# AdaptorEthernet485.net
KiCad netlist of a schematic drawn in EAGLE
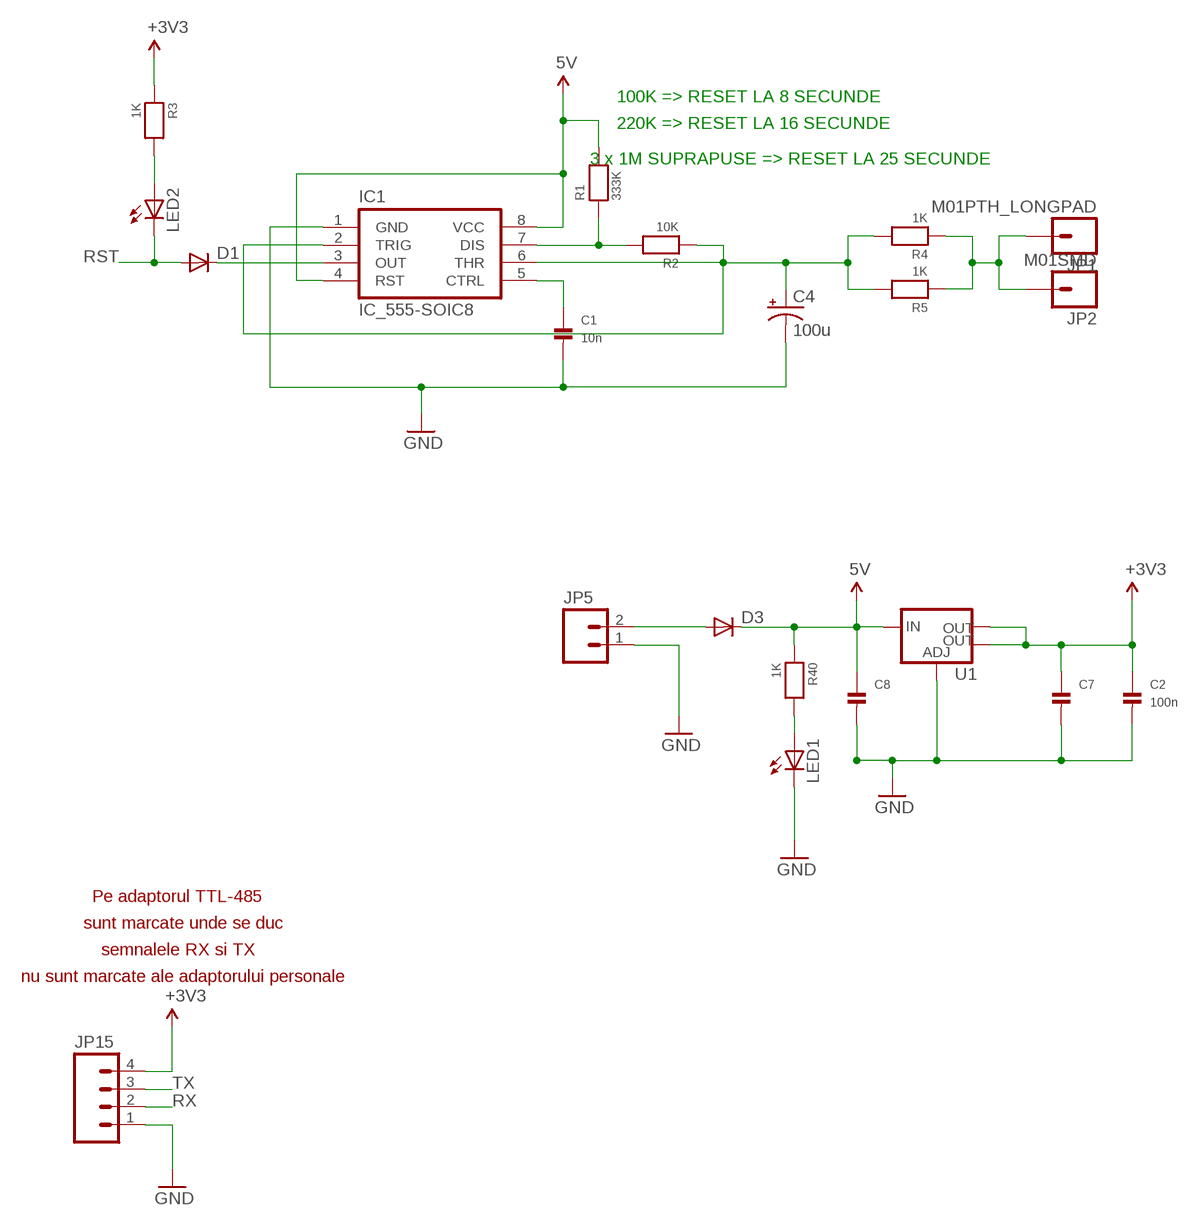
[diagram p0: schematic, sheet 1]

(export (version "E")
  (design (tool "Eeschema 10.0.6"))
  (components
    (comp (ref "C1")
      (value "10n")
      (footprint "eagle-import:_0805MP")
      (libsource (lib "eagle-import") (part "CAP_CERAMIC_0805MP"))
    )
    (comp (ref "C2")
      (value "100n")
      (footprint "eagle-import:_0805MP")
      (libsource (lib "eagle-import") (part "CAP_CERAMIC_0805MP"))
    )
    (comp (ref "C4")
      (value "100u")
      (footprint "eagle-import:CPOL-RADIAL-10UF-25V")
      (libsource (lib "eagle-import") (part "CAP_POLPTH2"))
    )
    (comp (ref "C7")
      (value "CAP_CERAMIC1206")
      (footprint "eagle-import:1206")
      (libsource (lib "eagle-import") (part "CAP_CERAMIC1206"))
    )
    (comp (ref "C8")
      (value "CAP_CERAMIC1206")
      (footprint "eagle-import:1206")
      (libsource (lib "eagle-import") (part "CAP_CERAMIC1206"))
    )
    (comp (ref "D1")
      (value "DIODE-DO214AA")
      (footprint "eagle-import:DO214AA")
      (libsource (lib "eagle-import") (part "DIODE-DO214AA"))
    )
    (comp (ref "D3")
      (value "DIODE-DO214AA")
      (footprint "eagle-import:DO214AA")
      (libsource (lib "eagle-import") (part "DIODE-DO214AA"))
    )
    (comp (ref "IC1")
      (value "IC_555-SOIC8")
      (footprint "eagle-import:SOIC-8")
      (libsource (lib "eagle-import") (part "IC_555-SOIC8"))
    )
    (comp (ref "JP1")
      (value "M01PTH_LONGPAD")
      (footprint "eagle-import:1X01_LONGPAD")
      (libsource (lib "eagle-import") (part "M01PTH_LONGPAD"))
    )
    (comp (ref "JP2")
      (value "M01SMD")
      (footprint "eagle-import:LUXEON-PAD")
      (libsource (lib "eagle-import") (part "M01SMD"))
    )
    (comp (ref "JP5")
      (value "M02PTH4")
      (footprint "eagle-import:1X02_XTRA_BIG")
      (libsource (lib "eagle-import") (part "M02PTH4"))
    )
    (comp (ref "JP15")
      (value "M04LONGPADS")
      (footprint "eagle-import:1X04_LONGPADS")
      (libsource (lib "eagle-import") (part "M04LONGPADS"))
    )
    (comp (ref "LED1")
      (value "LED-3MM-NO_SILK")
      (footprint "eagle-import:LED3MM-NS")
      (libsource (lib "eagle-import") (part "LED-3MM-NO_SILK"))
    )
    (comp (ref "LED2")
      (value "LED-3MM-NO_SILK")
      (footprint "eagle-import:LED3MM-NS")
      (libsource (lib "eagle-import") (part "LED-3MM-NO_SILK"))
    )
    (comp (ref "R1")
      (value "333K")
      (footprint "eagle-import:_0805MP")
      (libsource (lib "eagle-import") (part "RESISTOR_0805MP"))
    )
    (comp (ref "R2")
      (value "10K")
      (footprint "eagle-import:_0805MP")
      (libsource (lib "eagle-import") (part "RESISTOR_0805MP"))
    )
    (comp (ref "R3")
      (value "1K")
      (footprint "eagle-import:_0805MP")
      (libsource (lib "eagle-import") (part "RESISTOR_0805MP"))
    )
    (comp (ref "R4")
      (value "1K")
      (footprint "eagle-import:_0805MP")
      (libsource (lib "eagle-import") (part "RESISTOR_0805MP"))
    )
    (comp (ref "R5")
      (value "1K")
      (footprint "eagle-import:_0805MP")
      (libsource (lib "eagle-import") (part "RESISTOR_0805MP"))
    )
    (comp (ref "R40")
      (value "1K")
      (footprint "eagle-import:_0805MP")
      (libsource (lib "eagle-import") (part "RESISTOR_0805MP"))
    )
    (comp (ref "U1")
      (value "V_REG_LM1117SOT223")
      (footprint "eagle-import:SOT223")
      (libsource (lib "eagle-import") (part "V_REG_LM1117SOT223"))
    )
  )
  (nets
    (net (code "1") (name "+3V3") (class "Default")
      (node (ref "C2") (pin "1") (pinfunction "P$1_1") (pintype "passive"))
      (node (ref "C7") (pin "1") (pinfunction "P$1_1") (pintype "passive"))
      (node (ref "JP15") (pin "4") (pinfunction "4_4") (pintype "passive"))
      (node (ref "R3") (pin "1") (pinfunction "1_1") (pintype "passive"))
      (node (ref "U1") (pin "2") (pinfunction "OUT_2") (pintype "output"))
      (node (ref "U1") (pin "4") (pinfunction "OUT_4") (pintype "output"))
    )
    (net (code "2") (name "/RST") (class "Default")
      (node (ref "D1") (pin "A") (pinfunction "A_A") (pintype "passive"))
      (node (ref "LED2") (pin "K") (pinfunction "C_K") (pintype "passive"))
    )
    (net (code "3") (name "/RX") (class "Default")
      (node (ref "JP15") (pin "2") (pinfunction "2_2") (pintype "passive"))
    )
    (net (code "4") (name "/TX") (class "Default")
      (node (ref "JP15") (pin "3") (pinfunction "3_3") (pintype "passive"))
    )
    (net (code "5") (name "5V") (class "Default")
      (node (ref "C8") (pin "1") (pinfunction "P$1_1") (pintype "passive"))
      (node (ref "D3") (pin "C") (pinfunction "C_C") (pintype "passive"))
      (node (ref "IC1") (pin "4") (pinfunction "RST_4") (pintype "input"))
      (node (ref "IC1") (pin "8") (pinfunction "VCC_8") (pintype "power_in"))
      (node (ref "R1") (pin "2") (pinfunction "2_2") (pintype "passive"))
      (node (ref "R40") (pin "1") (pinfunction "1_1") (pintype "passive"))
      (node (ref "U1") (pin "3") (pinfunction "IN_3") (pintype "input"))
    )
    (net (code "6") (name "GND") (class "Default")
      (node (ref "C1") (pin "2") (pinfunction "P$2_2") (pintype "passive"))
      (node (ref "C2") (pin "2") (pinfunction "P$2_2") (pintype "passive"))
      (node (ref "C4") (pin "2") (pinfunction "-_2") (pintype "passive"))
      (node (ref "C7") (pin "2") (pinfunction "P$2_2") (pintype "passive"))
      (node (ref "C8") (pin "2") (pinfunction "P$2_2") (pintype "passive"))
      (node (ref "IC1") (pin "1") (pinfunction "GND_1") (pintype "power_in"))
      (node (ref "JP15") (pin "1") (pinfunction "1_1") (pintype "passive"))
      (node (ref "JP5") (pin "1") (pinfunction "1_1") (pintype "passive"))
      (node (ref "LED1") (pin "K") (pinfunction "C_K") (pintype "passive"))
      (node (ref "U1") (pin "1") (pinfunction "ADJ_1") (pintype "input"))
    )
    (net (code "7") (name "Net-(C1-P$1)") (class "Default")
      (node (ref "C1") (pin "1") (pinfunction "P$1_1") (pintype "passive"))
      (node (ref "IC1") (pin "5") (pinfunction "CTRL_5") (pintype "power_in"))
    )
    (net (code "8") (name "Net-(C4-+)") (class "Default")
      (node (ref "C4") (pin "1") (pinfunction "+_1") (pintype "passive"))
      (node (ref "IC1") (pin "2") (pinfunction "TRIG_2") (pintype "input"))
      (node (ref "IC1") (pin "6") (pinfunction "THR_6") (pintype "input"))
      (node (ref "R2") (pin "1") (pinfunction "1_1") (pintype "passive"))
      (node (ref "R4") (pin "2") (pinfunction "2_2") (pintype "passive"))
      (node (ref "R5") (pin "2") (pinfunction "2_2") (pintype "passive"))
    )
    (net (code "9") (name "Net-(D3-PadA)") (class "Default")
      (node (ref "D3") (pin "A") (pinfunction "A_A") (pintype "passive"))
      (node (ref "JP5") (pin "2") (pinfunction "2_2") (pintype "passive"))
    )
    (net (code "10") (name "Net-(IC1-DIS)") (class "Default")
      (node (ref "IC1") (pin "7") (pinfunction "DIS_7") (pintype "input"))
      (node (ref "R1") (pin "1") (pinfunction "1_1") (pintype "passive"))
      (node (ref "R2") (pin "2") (pinfunction "2_2") (pintype "passive"))
    )
    (net (code "11") (name "Net-(IC1-OUT)") (class "Default")
      (node (ref "D1") (pin "C") (pinfunction "C_C") (pintype "passive"))
      (node (ref "IC1") (pin "3") (pinfunction "OUT_3") (pintype "output"))
    )
    (net (code "12") (name "Net-(JP2-1)") (class "Default")
      (node (ref "JP1") (pin "1") (pinfunction "1_1") (pintype "passive"))
      (node (ref "JP2") (pin "P$1") (pinfunction "1_P$1") (pintype "passive"))
      (node (ref "R4") (pin "1") (pinfunction "1_1") (pintype "passive"))
      (node (ref "R5") (pin "1") (pinfunction "1_1") (pintype "passive"))
    )
    (net (code "13") (name "Net-(LED1-PadA)") (class "Default")
      (node (ref "LED1") (pin "A") (pinfunction "A_A") (pintype "passive"))
      (node (ref "R40") (pin "2") (pinfunction "2_2") (pintype "passive"))
    )
    (net (code "14") (name "Net-(LED2-PadA)") (class "Default")
      (node (ref "LED2") (pin "A") (pinfunction "A_A") (pintype "passive"))
      (node (ref "R3") (pin "2") (pinfunction "2_2") (pintype "passive"))
    )
  )
)
